# drvelocity.net
KiCad netlist of a schematic drawn in EAGLE
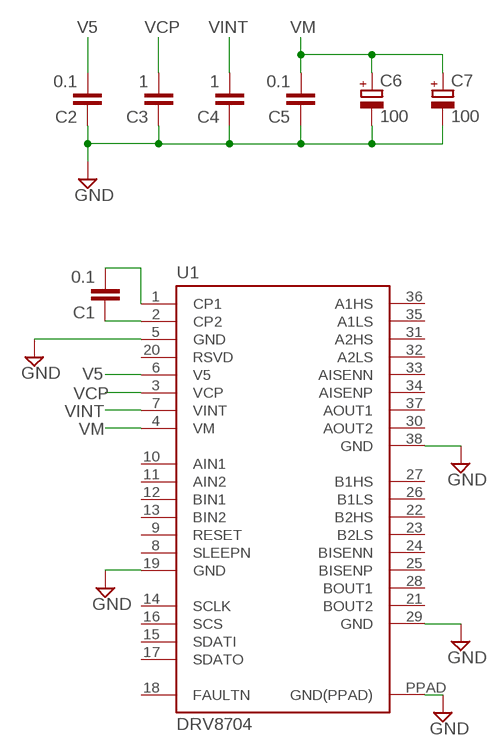
[diagram p0: schematic, sheet 1]

(export (version "E")
  (design (tool "Eeschema 10.0.6"))
  (components
    (comp (ref "C1")
      (value "0.1")
      (footprint "eagle-import:C0402")
      (libsource (lib "eagle-import") (part "C-EUC0402"))
    )
    (comp (ref "C2")
      (value "0.1")
      (footprint "eagle-import:C0402")
      (libsource (lib "eagle-import") (part "C-EUC0402"))
    )
    (comp (ref "C3")
      (value "1")
      (footprint "eagle-import:C0402")
      (libsource (lib "eagle-import") (part "C-EUC0402"))
    )
    (comp (ref "C4")
      (value "1")
      (footprint "eagle-import:C0402")
      (libsource (lib "eagle-import") (part "C-EUC0402"))
    )
    (comp (ref "C5")
      (value "0.1")
      (footprint "eagle-import:C0402")
      (libsource (lib "eagle-import") (part "C-EUC0402"))
    )
    (comp (ref "C6")
      (value "100")
      (footprint "eagle-import:E3,5-10")
      (libsource (lib "eagle-import") (part "CPOL-EUE3.5-10"))
    )
    (comp (ref "C7")
      (value "100")
      (footprint "eagle-import:E3,5-10")
      (libsource (lib "eagle-import") (part "CPOL-EUE3.5-10"))
    )
    (comp (ref "U1")
      (value "DRV8704")
      (footprint "eagle-import:HTSSOP-38")
      (libsource (lib "eagle-import") (part "DRV8704"))
    )
  )
  (nets
    (net (code "1") (name "/V5") (class "Default")
      (node (ref "C2") (pin "2") (pinfunction "2_2") (pintype "passive"))
      (node (ref "U1") (pin "6") (pinfunction "V5_6") (pintype "bidirectional"))
    )
    (net (code "2") (name "/VCP") (class "Default")
      (node (ref "C3") (pin "2") (pinfunction "2_2") (pintype "passive"))
      (node (ref "U1") (pin "3") (pinfunction "VCP_3") (pintype "bidirectional"))
    )
    (net (code "3") (name "/VINT") (class "Default")
      (node (ref "C4") (pin "2") (pinfunction "2_2") (pintype "passive"))
      (node (ref "U1") (pin "7") (pinfunction "VINT_7") (pintype "bidirectional"))
    )
    (net (code "4") (name "/VM") (class "Default")
      (node (ref "C5") (pin "2") (pinfunction "2_2") (pintype "passive"))
      (node (ref "C6") (pin "+") (pinfunction "+_+") (pintype "passive"))
      (node (ref "C7") (pin "+") (pinfunction "+_+") (pintype "passive"))
      (node (ref "U1") (pin "4") (pinfunction "VM_4") (pintype "bidirectional"))
    )
    (net (code "5") (name "GND") (class "Default")
      (node (ref "C2") (pin "1") (pinfunction "1_1") (pintype "passive"))
      (node (ref "C3") (pin "1") (pinfunction "1_1") (pintype "passive"))
      (node (ref "C4") (pin "1") (pinfunction "1_1") (pintype "passive"))
      (node (ref "C5") (pin "1") (pinfunction "1_1") (pintype "passive"))
      (node (ref "C6") (pin "-") (pinfunction "-_-") (pintype "passive"))
      (node (ref "C7") (pin "-") (pinfunction "-_-") (pintype "passive"))
      (node (ref "U1") (pin "19") (pinfunction "GND_19") (pintype "bidirectional"))
      (node (ref "U1") (pin "29") (pinfunction "GND_29") (pintype "bidirectional"))
      (node (ref "U1") (pin "38") (pinfunction "GND_38") (pintype "bidirectional"))
      (node (ref "U1") (pin "5") (pinfunction "GND_5") (pintype "bidirectional"))
      (node (ref "U1") (pin "PPAD") (pinfunction "GND(PPAD)_PPAD") (pintype "bidirectional"))
    )
    (net (code "6") (name "Net-(U1-CP1)") (class "Default")
      (node (ref "C1") (pin "2") (pinfunction "2_2") (pintype "passive"))
      (node (ref "U1") (pin "1") (pinfunction "CP1_1") (pintype "bidirectional"))
    )
    (net (code "7") (name "Net-(U1-CP2)") (class "Default")
      (node (ref "C1") (pin "1") (pinfunction "1_1") (pintype "passive"))
      (node (ref "U1") (pin "2") (pinfunction "CP2_2") (pintype "bidirectional"))
    )
    (net (code "8") (name "unconnected-(U1-A1HS-Pad36)") (class "Default")
      (node (ref "U1") (pin "36") (pinfunction "A1HS_36") (pintype "bidirectional"))
    )
    (net (code "9") (name "unconnected-(U1-A1LS-Pad35)") (class "Default")
      (node (ref "U1") (pin "35") (pinfunction "A1LS_35") (pintype "bidirectional"))
    )
    (net (code "10") (name "unconnected-(U1-A2HS-Pad31)") (class "Default")
      (node (ref "U1") (pin "31") (pinfunction "A2HS_31") (pintype "bidirectional"))
    )
    (net (code "11") (name "unconnected-(U1-A2LS-Pad32)") (class "Default")
      (node (ref "U1") (pin "32") (pinfunction "A2LS_32") (pintype "bidirectional"))
    )
    (net (code "12") (name "unconnected-(U1-AIN1-Pad10)") (class "Default")
      (node (ref "U1") (pin "10") (pinfunction "AIN1_10") (pintype "bidirectional"))
    )
    (net (code "13") (name "unconnected-(U1-AIN2-Pad11)") (class "Default")
      (node (ref "U1") (pin "11") (pinfunction "AIN2_11") (pintype "bidirectional"))
    )
    (net (code "14") (name "unconnected-(U1-AISENN-Pad33)") (class "Default")
      (node (ref "U1") (pin "33") (pinfunction "AISENN_33") (pintype "bidirectional"))
    )
    (net (code "15") (name "unconnected-(U1-AISENP-Pad34)") (class "Default")
      (node (ref "U1") (pin "34") (pinfunction "AISENP_34") (pintype "bidirectional"))
    )
    (net (code "16") (name "unconnected-(U1-AOUT1-Pad37)") (class "Default")
      (node (ref "U1") (pin "37") (pinfunction "AOUT1_37") (pintype "bidirectional"))
    )
    (net (code "17") (name "unconnected-(U1-AOUT2-Pad30)") (class "Default")
      (node (ref "U1") (pin "30") (pinfunction "AOUT2_30") (pintype "bidirectional"))
    )
    (net (code "18") (name "unconnected-(U1-B1HS-Pad27)") (class "Default")
      (node (ref "U1") (pin "27") (pinfunction "B1HS_27") (pintype "bidirectional"))
    )
    (net (code "19") (name "unconnected-(U1-B1LS-Pad26)") (class "Default")
      (node (ref "U1") (pin "26") (pinfunction "B1LS_26") (pintype "bidirectional"))
    )
    (net (code "20") (name "unconnected-(U1-B2HS-Pad22)") (class "Default")
      (node (ref "U1") (pin "22") (pinfunction "B2HS_22") (pintype "bidirectional"))
    )
    (net (code "21") (name "unconnected-(U1-B2LS-Pad23)") (class "Default")
      (node (ref "U1") (pin "23") (pinfunction "B2LS_23") (pintype "bidirectional"))
    )
    (net (code "22") (name "unconnected-(U1-BIN1-Pad12)") (class "Default")
      (node (ref "U1") (pin "12") (pinfunction "BIN1_12") (pintype "bidirectional"))
    )
    (net (code "23") (name "unconnected-(U1-BIN2-Pad13)") (class "Default")
      (node (ref "U1") (pin "13") (pinfunction "BIN2_13") (pintype "bidirectional"))
    )
    (net (code "24") (name "unconnected-(U1-BISENN-Pad24)") (class "Default")
      (node (ref "U1") (pin "24") (pinfunction "BISENN_24") (pintype "bidirectional"))
    )
    (net (code "25") (name "unconnected-(U1-BISENP-Pad25)") (class "Default")
      (node (ref "U1") (pin "25") (pinfunction "BISENP_25") (pintype "bidirectional"))
    )
    (net (code "26") (name "unconnected-(U1-BOUT1-Pad28)") (class "Default")
      (node (ref "U1") (pin "28") (pinfunction "BOUT1_28") (pintype "bidirectional"))
    )
    (net (code "27") (name "unconnected-(U1-BOUT2-Pad21)") (class "Default")
      (node (ref "U1") (pin "21") (pinfunction "BOUT2_21") (pintype "bidirectional"))
    )
    (net (code "28") (name "unconnected-(U1-FAULTN-Pad18)") (class "Default")
      (node (ref "U1") (pin "18") (pinfunction "FAULTN_18") (pintype "bidirectional"))
    )
    (net (code "29") (name "unconnected-(U1-RESET-Pad9)") (class "Default")
      (node (ref "U1") (pin "9") (pinfunction "RESET_9") (pintype "bidirectional"))
    )
    (net (code "30") (name "unconnected-(U1-RSVD-Pad20)") (class "Default")
      (node (ref "U1") (pin "20") (pinfunction "RSVD_20") (pintype "bidirectional"))
    )
    (net (code "31") (name "unconnected-(U1-SCLK-Pad14)") (class "Default")
      (node (ref "U1") (pin "14") (pinfunction "SCLK_14") (pintype "bidirectional"))
    )
    (net (code "32") (name "unconnected-(U1-SCS-Pad16)") (class "Default")
      (node (ref "U1") (pin "16") (pinfunction "SCS_16") (pintype "bidirectional"))
    )
    (net (code "33") (name "unconnected-(U1-SDATI-Pad15)") (class "Default")
      (node (ref "U1") (pin "15") (pinfunction "SDATI_15") (pintype "bidirectional"))
    )
    (net (code "34") (name "unconnected-(U1-SDATO-Pad17)") (class "Default")
      (node (ref "U1") (pin "17") (pinfunction "SDATO_17") (pintype "bidirectional"))
    )
    (net (code "35") (name "unconnected-(U1-SLEEPN-Pad8)") (class "Default")
      (node (ref "U1") (pin "8") (pinfunction "SLEEPN_8") (pintype "bidirectional"))
    )
  )
)
